# PCB-SLIDER60.net
KiCad netlist of a schematic drawn in EAGLE
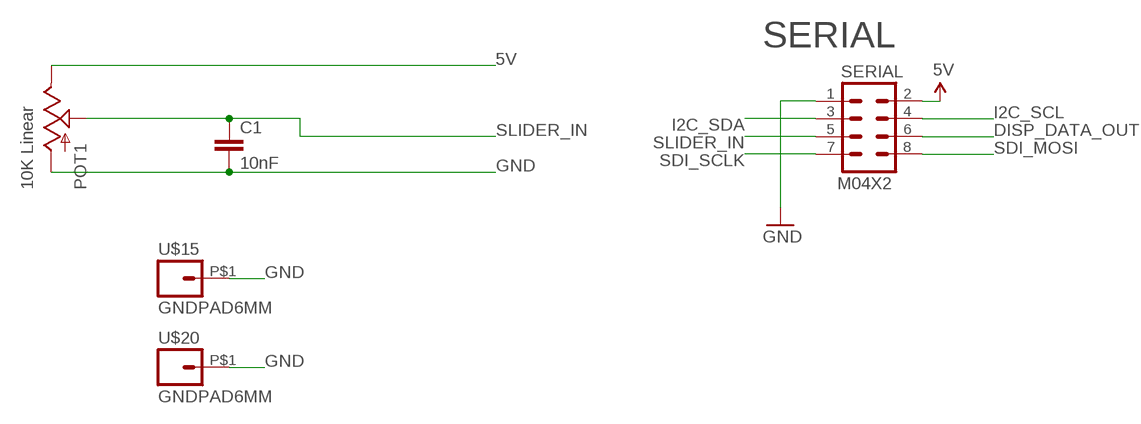
[diagram p0: schematic, sheet 1]

(export (version "E")
  (design (tool "Eeschema 10.0.6"))
  (components
    (comp (ref "C1")
      (value "10nF")
      (footprint "eagle-import:0603-CAP")
      (libsource (lib "eagle-import") (part "CAP0603-CAP"))
    )
    (comp (ref "POT1")
      (value "10K Linear")
      (footprint "eagle-import:SLIDER60")
      (libsource (lib "eagle-import") (part "SLIDER60"))
    )
    (comp (ref "SERIAL")
      (value "M04X2")
      (footprint "eagle-import:2X4")
      (libsource (lib "eagle-import") (part "M04X2"))
    )
    (comp (ref "U$15")
      (value "GNDPAD6MM")
      (footprint "eagle-import:3.2MMPAD6MM")
      (libsource (lib "eagle-import") (part "GNDPAD6MM"))
    )
    (comp (ref "U$20")
      (value "GNDPAD6MM")
      (footprint "eagle-import:3.2MMPAD6MM")
      (libsource (lib "eagle-import") (part "GNDPAD6MM"))
    )
  )
  (nets
    (net (code "1") (name "/DISP_DATA_OUT") (class "Default")
      (node (ref "SERIAL") (pin "6") (pinfunction "6_6") (pintype "passive"))
    )
    (net (code "2") (name "/I2C_SCL") (class "Default")
      (node (ref "SERIAL") (pin "4") (pinfunction "4_4") (pintype "passive"))
    )
    (net (code "3") (name "/I2C_SDA") (class "Default")
      (node (ref "SERIAL") (pin "3") (pinfunction "3_3") (pintype "passive"))
    )
    (net (code "4") (name "/SDI_MOSI") (class "Default")
      (node (ref "SERIAL") (pin "8") (pinfunction "8_8") (pintype "passive"))
    )
    (net (code "5") (name "/SDI_SCLK") (class "Default")
      (node (ref "SERIAL") (pin "7") (pinfunction "7_7") (pintype "passive"))
    )
    (net (code "6") (name "/SLIDER_IN") (class "Default")
      (node (ref "C1") (pin "1") (pinfunction "1_1") (pintype "passive"))
      (node (ref "POT1") (pin "2A") (pinfunction "S_2A") (pintype "passive"))
      (node (ref "SERIAL") (pin "5") (pinfunction "5_5") (pintype "passive"))
    )
    (net (code "7") (name "5V") (class "Default")
      (node (ref "POT1") (pin "1") (pinfunction "E_1") (pintype "passive"))
      (node (ref "SERIAL") (pin "2") (pinfunction "2_2") (pintype "passive"))
    )
    (net (code "8") (name "GND") (class "Default")
      (node (ref "C1") (pin "2") (pinfunction "2_2") (pintype "passive"))
      (node (ref "POT1") (pin "3") (pinfunction "A_3") (pintype "passive"))
      (node (ref "SERIAL") (pin "1") (pinfunction "1_1") (pintype "passive"))
      (node (ref "U$15") (pin "P$1") (pinfunction "1_P$1") (pintype "passive"))
      (node (ref "U$20") (pin "P$1") (pinfunction "1_P$1") (pintype "passive"))
    )
  )
)
